# kanal_v2.net
KiCad netlist of a schematic drawn in EAGLE
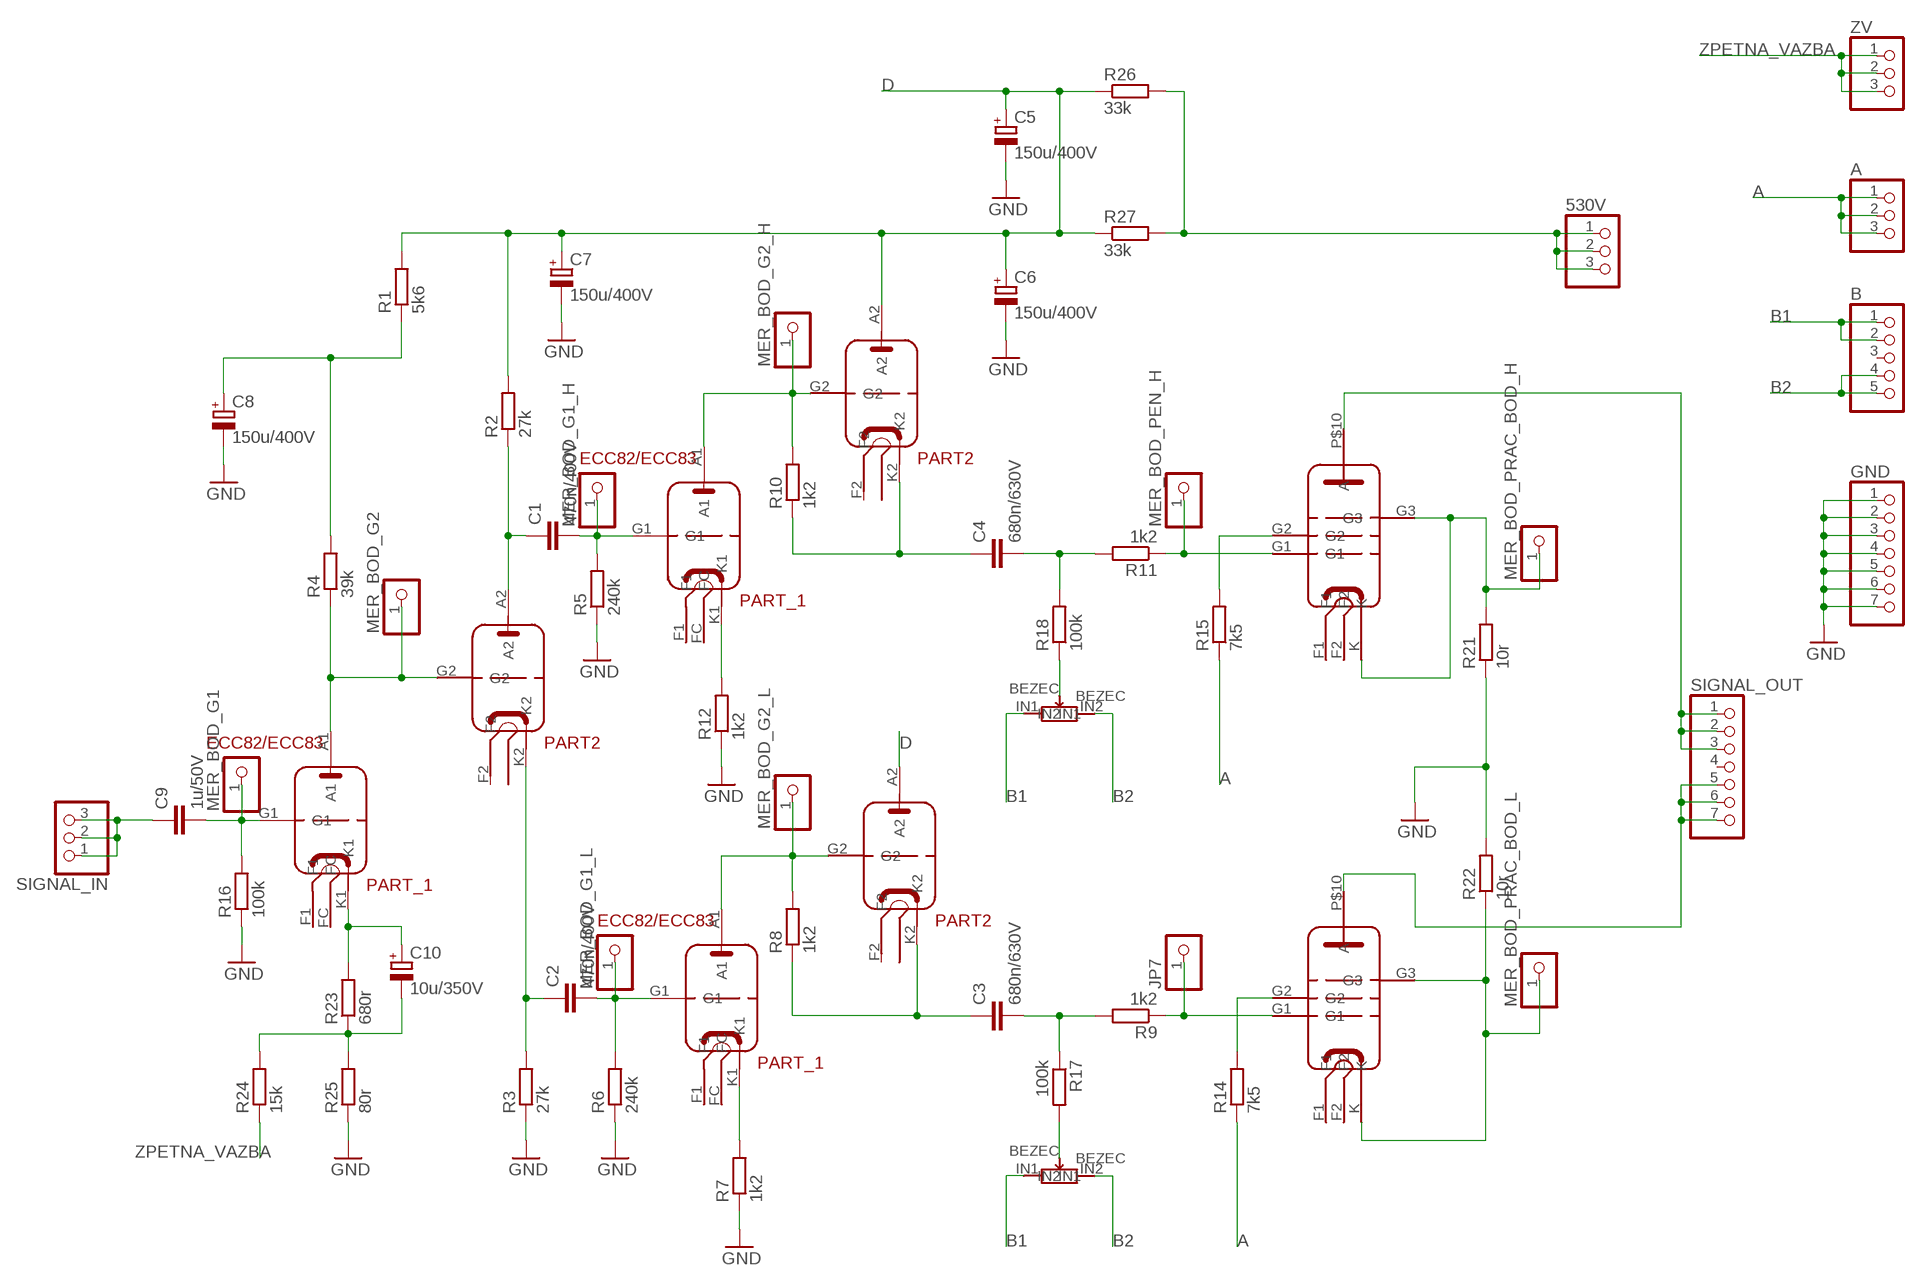
[diagram p0: schematic, sheet 1]

(export (version "E")
  (design (tool "Eeschema 10.0.6"))
  (components
    (comp (ref "530V")
      (value "PINHD-1X3")
      (footprint "eagle-import:1X03")
      (libsource (lib "eagle-import") (part "PINHD-1X3"))
    )
    (comp (ref "A")
      (value "PINHD-1X3")
      (footprint "eagle-import:1X03")
      (libsource (lib "eagle-import") (part "PINHD-1X3"))
    )
    (comp (ref "B")
      (value "PINHD-1X5")
      (footprint "eagle-import:1X05")
      (libsource (lib "eagle-import") (part "PINHD-1X5"))
    )
    (comp (ref "C1")
      (value "470n/400V")
      (footprint "eagle-import:C15B7")
      (libsource (lib "eagle-import") (part "C15/7"))
    )
    (comp (ref "C2")
      (value "470n/400V")
      (footprint "eagle-import:C15B7")
      (libsource (lib "eagle-import") (part "C15/7"))
    )
    (comp (ref "C3")
      (value "680n/630V")
      (footprint "eagle-import:C27.5B11")
      (libsource (lib "eagle-import") (part "C27/11"))
    )
    (comp (ref "C4")
      (value "680n/630V")
      (footprint "eagle-import:C27.5B11")
      (libsource (lib "eagle-import") (part "C27/11"))
    )
    (comp (ref "C5")
      (value "150u/400V")
      (footprint "eagle-import:EB25D")
      (libsource (lib "eagle-import") (part "resistor_CPOL-EUE10-25"))
    )
    (comp (ref "C6")
      (value "150u/400V")
      (footprint "eagle-import:EB25D")
      (libsource (lib "eagle-import") (part "resistor_CPOL-EUE10-25"))
    )
    (comp (ref "C7")
      (value "150u/400V")
      (footprint "eagle-import:EB25D")
      (libsource (lib "eagle-import") (part "resistor_CPOL-EUE10-25"))
    )
    (comp (ref "C8")
      (value "150u/400V")
      (footprint "eagle-import:EB25D")
      (libsource (lib "eagle-import") (part "resistor_CPOL-EUE10-25"))
    )
    (comp (ref "C9")
      (value "1u/50V")
      (footprint "eagle-import:C5B3.5")
      (libsource (lib "eagle-import") (part "C5/3.5"))
    )
    (comp (ref "C10")
      (value "10u/350V")
      (footprint "eagle-import:E5-10,5")
      (libsource (lib "eagle-import") (part "CPOL-EUE5-10.5"))
    )
    (comp (ref "GND")
      (value "PINHD-1X7")
      (footprint "eagle-import:1X07")
      (libsource (lib "eagle-import") (part "PINHD-1X7"))
    )
    (comp (ref "JP7")
      (value "PINHD-1X1")
      (footprint "eagle-import:1X01")
      (libsource (lib "eagle-import") (part "PINHD-1X1"))
    )
    (comp (ref "MER_BOD_G1")
      (value "PINHD-1X1")
      (footprint "eagle-import:1X01")
      (libsource (lib "eagle-import") (part "PINHD-1X1"))
    )
    (comp (ref "MER_BOD_G1_H")
      (value "PINHD-1X1")
      (footprint "eagle-import:1X01")
      (libsource (lib "eagle-import") (part "PINHD-1X1"))
    )
    (comp (ref "MER_BOD_G1_L")
      (value "PINHD-1X1")
      (footprint "eagle-import:1X01")
      (libsource (lib "eagle-import") (part "PINHD-1X1"))
    )
    (comp (ref "MER_BOD_G2")
      (value "PINHD-1X1")
      (footprint "eagle-import:1X01")
      (libsource (lib "eagle-import") (part "PINHD-1X1"))
    )
    (comp (ref "MER_BOD_G2_H")
      (value "PINHD-1X1")
      (footprint "eagle-import:1X01")
      (libsource (lib "eagle-import") (part "PINHD-1X1"))
    )
    (comp (ref "MER_BOD_G2_L")
      (value "PINHD-1X1")
      (footprint "eagle-import:1X01")
      (libsource (lib "eagle-import") (part "PINHD-1X1"))
    )
    (comp (ref "MER_BOD_PEN_H")
      (value "PINHD-1X1")
      (footprint "eagle-import:1X01")
      (libsource (lib "eagle-import") (part "PINHD-1X1"))
    )
    (comp (ref "MER_BOD_PRAC_BOD_H")
      (value "PINHD-1X1")
      (footprint "eagle-import:1X01")
      (libsource (lib "eagle-import") (part "PINHD-1X1"))
    )
    (comp (ref "MER_BOD_PRAC_BOD_L")
      (value "PINHD-1X1")
      (footprint "eagle-import:1X01")
      (libsource (lib "eagle-import") (part "PINHD-1X1"))
    )
    (comp (ref "R1")
      (value "5k6")
      (footprint "eagle-import:0309_10")
      (libsource (lib "eagle-import") (part "R-EU_0309/10"))
    )
    (comp (ref "R2")
      (value "27k")
      (footprint "eagle-import:0309_10")
      (libsource (lib "eagle-import") (part "R-EU_0309/10"))
    )
    (comp (ref "R3")
      (value "27k")
      (footprint "eagle-import:0309_10")
      (libsource (lib "eagle-import") (part "R-EU_0309/10"))
    )
    (comp (ref "R4")
      (value "39k")
      (footprint "eagle-import:0309_10")
      (libsource (lib "eagle-import") (part "R-EU_0309/10"))
    )
    (comp (ref "R5")
      (value "240k")
      (footprint "eagle-import:0309_10")
      (libsource (lib "eagle-import") (part "R-EU_0309/10"))
    )
    (comp (ref "R6")
      (value "240k")
      (footprint "eagle-import:0309_10")
      (libsource (lib "eagle-import") (part "R-EU_0309/10"))
    )
    (comp (ref "R7")
      (value "1k2")
      (footprint "eagle-import:0309_10")
      (libsource (lib "eagle-import") (part "R-EU_0309/10"))
    )
    (comp (ref "R8")
      (value "1k2")
      (footprint "eagle-import:0309_10")
      (libsource (lib "eagle-import") (part "R-EU_0309/10"))
    )
    (comp (ref "R9")
      (value "1k2")
      (footprint "eagle-import:0309_10")
      (libsource (lib "eagle-import") (part "R-EU_0309/10"))
    )
    (comp (ref "R10")
      (value "1k2")
      (footprint "eagle-import:0309_10")
      (libsource (lib "eagle-import") (part "R-EU_0309/10"))
    )
    (comp (ref "R11")
      (value "1k2")
      (footprint "eagle-import:0309_10")
      (libsource (lib "eagle-import") (part "R-EU_0309/10"))
    )
    (comp (ref "R12")
      (value "1k2")
      (footprint "eagle-import:0309_10")
      (libsource (lib "eagle-import") (part "R-EU_0309/10"))
    )
    (comp (ref "R14")
      (value "7k5")
      (footprint "eagle-import:0309_10")
      (libsource (lib "eagle-import") (part "R-EU_0309/10"))
    )
    (comp (ref "R15")
      (value "7k5")
      (footprint "eagle-import:0309_10")
      (libsource (lib "eagle-import") (part "R-EU_0309/10"))
    )
    (comp (ref "R16")
      (value "100k")
      (footprint "eagle-import:0309_10")
      (libsource (lib "eagle-import") (part "R-EU_0309/10"))
    )
    (comp (ref "R17")
      (value "100k")
      (footprint "eagle-import:0309_10")
      (libsource (lib "eagle-import") (part "R-EU_0309/10"))
    )
    (comp (ref "R18")
      (value "100k")
      (footprint "eagle-import:0309_10")
      (libsource (lib "eagle-import") (part "R-EU_0309/10"))
    )
    (comp (ref "R21")
      (value "10r")
      (footprint "eagle-import:0309_10")
      (libsource (lib "eagle-import") (part "R-EU_0309/10"))
    )
    (comp (ref "R22")
      (value "10r")
      (footprint "eagle-import:0309_10")
      (libsource (lib "eagle-import") (part "R-EU_0309/10"))
    )
    (comp (ref "R23")
      (value "680r")
      (footprint "eagle-import:0309_10")
      (libsource (lib "eagle-import") (part "R-EU_0309/10"))
    )
    (comp (ref "R24")
      (value "15k")
      (footprint "eagle-import:0309_10")
      (libsource (lib "eagle-import") (part "R-EU_0309/10"))
    )
    (comp (ref "R25")
      (value "80r")
      (footprint "eagle-import:0309_10")
      (libsource (lib "eagle-import") (part "R-EU_0309/10"))
    )
    (comp (ref "R26")
      (value "33k")
      (footprint "eagle-import:0309_10")
      (libsource (lib "eagle-import") (part "R-EU_0309/10"))
    )
    (comp (ref "R27")
      (value "33k")
      (footprint "eagle-import:0309_10")
      (libsource (lib "eagle-import") (part "R-EU_0309/10"))
    )
    (comp (ref "SIGNAL_IN")
      (value "PINHD-1X3")
      (footprint "eagle-import:1X03")
      (libsource (lib "eagle-import") (part "PINHD-1X3"))
    )
    (comp (ref "SIGNAL_OUT")
      (value "PINHD-1X7")
      (footprint "eagle-import:1X07")
      (libsource (lib "eagle-import") (part "PINHD-1X7"))
    )
    (comp (ref "U$1")
      (value "ECC82")
      (footprint "eagle-import:ECC82_PACKAGE")
      (libsource (lib "eagle-import") (part "ECC82"))
    )
    (comp (ref "U$2")
      (value "ECC83")
      (footprint "eagle-import:ECC82_PACKAGE")
      (libsource (lib "eagle-import") (part "ECC83"))
    )
    (comp (ref "U$3")
      (value "ECC83")
      (footprint "eagle-import:ECC82_PACKAGE")
      (libsource (lib "eagle-import") (part "ECC83"))
    )
    (comp (ref "U$4")
      (value "PL509")
      (footprint "eagle-import:PL509_PACKAGE")
      (libsource (lib "eagle-import") (part "PL509"))
    )
    (comp (ref "U$5")
      (value "PL509")
      (footprint "eagle-import:PL509_PACKAGE")
      (libsource (lib "eagle-import") (part "PL509"))
    )
    (comp (ref "U$6")
      (value "TRIMMER")
      (footprint "eagle-import:TRIMMER_15X15_PACKAGE")
      (libsource (lib "eagle-import") (part "TRIMMER"))
    )
    (comp (ref "U$7")
      (value "TRIMMER")
      (footprint "eagle-import:TRIMMER_15X15_PACKAGE")
      (libsource (lib "eagle-import") (part "TRIMMER"))
    )
    (comp (ref "ZV")
      (value "PINHD-1X3")
      (footprint "eagle-import:1X03")
      (libsource (lib "eagle-import") (part "PINHD-1X3"))
    )
  )
  (nets
    (net (code "1") (name "/A") (class "Default")
      (node (ref "A") (pin "1") (pinfunction "1_1") (pintype "passive"))
      (node (ref "A") (pin "2") (pinfunction "2_2") (pintype "passive"))
      (node (ref "A") (pin "3") (pinfunction "3_3") (pintype "passive"))
      (node (ref "R14") (pin "1") (pinfunction "1_1") (pintype "passive"))
      (node (ref "R15") (pin "1") (pinfunction "1_1") (pintype "passive"))
    )
    (net (code "2") (name "/B1") (class "Default")
      (node (ref "B") (pin "1") (pinfunction "1_1") (pintype "passive"))
      (node (ref "B") (pin "2") (pinfunction "2_2") (pintype "passive"))
      (node (ref "U$6") (pin "IN1") (pinfunction "IN1_IN1") (pintype "bidirectional"))
      (node (ref "U$7") (pin "IN1") (pinfunction "IN1_IN1") (pintype "bidirectional"))
    )
    (net (code "3") (name "/B2") (class "Default")
      (node (ref "B") (pin "4") (pinfunction "4_4") (pintype "passive"))
      (node (ref "B") (pin "5") (pinfunction "5_5") (pintype "passive"))
      (node (ref "U$6") (pin "IN2") (pinfunction "IN2_IN2") (pintype "bidirectional"))
      (node (ref "U$7") (pin "IN2") (pinfunction "IN2_IN2") (pintype "bidirectional"))
    )
    (net (code "4") (name "/D") (class "Default")
      (node (ref "C5") (pin "+") (pinfunction "+_+") (pintype "passive"))
      (node (ref "C6") (pin "+") (pinfunction "+_+") (pintype "passive"))
      (node (ref "C7") (pin "+") (pinfunction "+_+") (pintype "passive"))
      (node (ref "R1") (pin "2") (pinfunction "2_2") (pintype "passive"))
      (node (ref "R2") (pin "2") (pinfunction "2_2") (pintype "passive"))
      (node (ref "R26") (pin "1") (pinfunction "1_1") (pintype "passive"))
      (node (ref "R27") (pin "1") (pinfunction "1_1") (pintype "passive"))
      (node (ref "U$2") (pin "A2") (pinfunction "A2_A2") (pintype "bidirectional"))
      (node (ref "U$3") (pin "A2") (pinfunction "A2_A2") (pintype "bidirectional"))
    )
    (net (code "5") (name "/ZPETNA_VAZBA") (class "Default")
      (node (ref "R24") (pin "1") (pinfunction "1_1") (pintype "passive"))
      (node (ref "ZV") (pin "1") (pinfunction "1_1") (pintype "passive"))
      (node (ref "ZV") (pin "2") (pinfunction "2_2") (pintype "passive"))
      (node (ref "ZV") (pin "3") (pinfunction "3_3") (pintype "passive"))
    )
    (net (code "6") (name "GND") (class "Default")
      (node (ref "C5") (pin "-") (pinfunction "-_-") (pintype "passive"))
      (node (ref "C6") (pin "-") (pinfunction "-_-") (pintype "passive"))
      (node (ref "C7") (pin "-") (pinfunction "-_-") (pintype "passive"))
      (node (ref "C8") (pin "-") (pinfunction "-_-") (pintype "passive"))
      (node (ref "GND") (pin "1") (pinfunction "1_1") (pintype "passive"))
      (node (ref "GND") (pin "2") (pinfunction "2_2") (pintype "passive"))
      (node (ref "GND") (pin "3") (pinfunction "3_3") (pintype "passive"))
      (node (ref "GND") (pin "4") (pinfunction "4_4") (pintype "passive"))
      (node (ref "GND") (pin "5") (pinfunction "5_5") (pintype "passive"))
      (node (ref "GND") (pin "6") (pinfunction "6_6") (pintype "passive"))
      (node (ref "GND") (pin "7") (pinfunction "7_7") (pintype "passive"))
      (node (ref "R12") (pin "1") (pinfunction "1_1") (pintype "passive"))
      (node (ref "R16") (pin "1") (pinfunction "1_1") (pintype "passive"))
      (node (ref "R21") (pin "1") (pinfunction "1_1") (pintype "passive"))
      (node (ref "R22") (pin "2") (pinfunction "2_2") (pintype "passive"))
      (node (ref "R25") (pin "1") (pinfunction "1_1") (pintype "passive"))
      (node (ref "R3") (pin "1") (pinfunction "1_1") (pintype "passive"))
      (node (ref "R5") (pin "1") (pinfunction "1_1") (pintype "passive"))
      (node (ref "R6") (pin "1") (pinfunction "1_1") (pintype "passive"))
      (node (ref "R7") (pin "1") (pinfunction "1_1") (pintype "passive"))
    )
    (net (code "7") (name "Net-(530V-Pad1)") (class "Default")
      (node (ref "530V") (pin "1") (pinfunction "1_1") (pintype "passive"))
      (node (ref "530V") (pin "2") (pinfunction "2_2") (pintype "passive"))
      (node (ref "530V") (pin "3") (pinfunction "3_3") (pintype "passive"))
      (node (ref "R26") (pin "2") (pinfunction "2_2") (pintype "passive"))
      (node (ref "R27") (pin "2") (pinfunction "2_2") (pintype "passive"))
    )
    (net (code "8") (name "Net-(C1-Pad1)") (class "Default")
      (node (ref "C1") (pin "1") (pinfunction "1_1") (pintype "passive"))
      (node (ref "R2") (pin "1") (pinfunction "1_1") (pintype "passive"))
      (node (ref "U$1") (pin "A2") (pinfunction "A2_A2") (pintype "bidirectional"))
    )
    (net (code "9") (name "Net-(C1-Pad2)") (class "Default")
      (node (ref "C1") (pin "2") (pinfunction "2_2") (pintype "passive"))
      (node (ref "MER_BOD_G1_H") (pin "1") (pinfunction "1_1") (pintype "passive"))
      (node (ref "R5") (pin "2") (pinfunction "2_2") (pintype "passive"))
      (node (ref "U$2") (pin "G1") (pinfunction "G1_G1") (pintype "bidirectional"))
    )
    (net (code "10") (name "Net-(C2-Pad1)") (class "Default")
      (node (ref "C2") (pin "1") (pinfunction "1_1") (pintype "passive"))
      (node (ref "R3") (pin "2") (pinfunction "2_2") (pintype "passive"))
      (node (ref "U$1") (pin "K2") (pinfunction "K2_K2") (pintype "bidirectional"))
    )
    (net (code "11") (name "Net-(C2-Pad2)") (class "Default")
      (node (ref "C2") (pin "2") (pinfunction "2_2") (pintype "passive"))
      (node (ref "MER_BOD_G1_L") (pin "1") (pinfunction "1_1") (pintype "passive"))
      (node (ref "R6") (pin "2") (pinfunction "2_2") (pintype "passive"))
      (node (ref "U$3") (pin "G1") (pinfunction "G1_G1") (pintype "bidirectional"))
    )
    (net (code "12") (name "Net-(C3-Pad1)") (class "Default")
      (node (ref "C3") (pin "1") (pinfunction "1_1") (pintype "passive"))
      (node (ref "R8") (pin "1") (pinfunction "1_1") (pintype "passive"))
      (node (ref "U$3") (pin "K2") (pinfunction "K2_K2") (pintype "bidirectional"))
    )
    (net (code "13") (name "Net-(C3-Pad2)") (class "Default")
      (node (ref "C3") (pin "2") (pinfunction "2_2") (pintype "passive"))
      (node (ref "R17") (pin "1") (pinfunction "1_1") (pintype "passive"))
      (node (ref "R9") (pin "2") (pinfunction "2_2") (pintype "passive"))
    )
    (net (code "14") (name "Net-(C4-Pad1)") (class "Default")
      (node (ref "C4") (pin "1") (pinfunction "1_1") (pintype "passive"))
      (node (ref "R10") (pin "1") (pinfunction "1_1") (pintype "passive"))
      (node (ref "U$2") (pin "K2") (pinfunction "K2_K2") (pintype "bidirectional"))
    )
    (net (code "15") (name "Net-(C4-Pad2)") (class "Default")
      (node (ref "C4") (pin "2") (pinfunction "2_2") (pintype "passive"))
      (node (ref "R11") (pin "2") (pinfunction "2_2") (pintype "passive"))
      (node (ref "R18") (pin "2") (pinfunction "2_2") (pintype "passive"))
    )
    (net (code "16") (name "Net-(C8-Pad+)") (class "Default")
      (node (ref "C8") (pin "+") (pinfunction "+_+") (pintype "passive"))
      (node (ref "R1") (pin "1") (pinfunction "1_1") (pintype "passive"))
      (node (ref "R4") (pin "2") (pinfunction "2_2") (pintype "passive"))
    )
    (net (code "17") (name "Net-(C9-Pad1)") (class "Default")
      (node (ref "C9") (pin "1") (pinfunction "1_1") (pintype "passive"))
      (node (ref "SIGNAL_IN") (pin "1") (pinfunction "1_1") (pintype "passive"))
      (node (ref "SIGNAL_IN") (pin "2") (pinfunction "2_2") (pintype "passive"))
      (node (ref "SIGNAL_IN") (pin "3") (pinfunction "3_3") (pintype "passive"))
    )
    (net (code "18") (name "Net-(C9-Pad2)") (class "Default")
      (node (ref "C9") (pin "2") (pinfunction "2_2") (pintype "passive"))
      (node (ref "MER_BOD_G1") (pin "1") (pinfunction "1_1") (pintype "passive"))
      (node (ref "R16") (pin "2") (pinfunction "2_2") (pintype "passive"))
      (node (ref "U$1") (pin "G1") (pinfunction "G1_G1") (pintype "bidirectional"))
    )
    (net (code "19") (name "Net-(C10-Pad+)") (class "Default")
      (node (ref "C10") (pin "+") (pinfunction "+_+") (pintype "passive"))
      (node (ref "R23") (pin "2") (pinfunction "2_2") (pintype "passive"))
      (node (ref "U$1") (pin "K1") (pinfunction "K1_K1") (pintype "bidirectional"))
    )
    (net (code "20") (name "Net-(C10-Pad-)") (class "Default")
      (node (ref "C10") (pin "-") (pinfunction "-_-") (pintype "passive"))
      (node (ref "R23") (pin "1") (pinfunction "1_1") (pintype "passive"))
      (node (ref "R24") (pin "2") (pinfunction "2_2") (pintype "passive"))
      (node (ref "R25") (pin "2") (pinfunction "2_2") (pintype "passive"))
    )
    (net (code "21") (name "Net-(JP7-Pad1)") (class "Default")
      (node (ref "JP7") (pin "1") (pinfunction "1_1") (pintype "passive"))
      (node (ref "R9") (pin "1") (pinfunction "1_1") (pintype "passive"))
      (node (ref "U$5") (pin "G1") (pinfunction "G1_G1") (pintype "bidirectional"))
    )
    (net (code "22") (name "Net-(MER_BOD_G2-Pad1)") (class "Default")
      (node (ref "MER_BOD_G2") (pin "1") (pinfunction "1_1") (pintype "passive"))
      (node (ref "R4") (pin "1") (pinfunction "1_1") (pintype "passive"))
      (node (ref "U$1") (pin "A1") (pinfunction "A1_A1") (pintype "bidirectional"))
      (node (ref "U$1") (pin "G2") (pinfunction "G2_G2") (pintype "bidirectional"))
    )
    (net (code "23") (name "Net-(MER_BOD_G2_H-Pad1)") (class "Default")
      (node (ref "MER_BOD_G2_H") (pin "1") (pinfunction "1_1") (pintype "passive"))
      (node (ref "R10") (pin "2") (pinfunction "2_2") (pintype "passive"))
      (node (ref "U$2") (pin "A1") (pinfunction "A1_A1") (pintype "bidirectional"))
      (node (ref "U$2") (pin "G2") (pinfunction "G2_G2") (pintype "bidirectional"))
    )
    (net (code "24") (name "Net-(MER_BOD_G2_L-Pad1)") (class "Default")
      (node (ref "MER_BOD_G2_L") (pin "1") (pinfunction "1_1") (pintype "passive"))
      (node (ref "R8") (pin "2") (pinfunction "2_2") (pintype "passive"))
      (node (ref "U$3") (pin "A1") (pinfunction "A1_A1") (pintype "bidirectional"))
      (node (ref "U$3") (pin "G2") (pinfunction "G2_G2") (pintype "bidirectional"))
    )
    (net (code "25") (name "Net-(MER_BOD_PEN_H-Pad1)") (class "Default")
      (node (ref "MER_BOD_PEN_H") (pin "1") (pinfunction "1_1") (pintype "passive"))
      (node (ref "R11") (pin "1") (pinfunction "1_1") (pintype "passive"))
      (node (ref "U$4") (pin "G1") (pinfunction "G1_G1") (pintype "bidirectional"))
    )
    (net (code "26") (name "Net-(MER_BOD_PRAC_BOD_H-Pad1)") (class "Default")
      (node (ref "MER_BOD_PRAC_BOD_H") (pin "1") (pinfunction "1_1") (pintype "passive"))
      (node (ref "R21") (pin "2") (pinfunction "2_2") (pintype "passive"))
      (node (ref "U$4") (pin "G3") (pinfunction "G3_G3") (pintype "bidirectional"))
      (node (ref "U$4") (pin "K") (pinfunction "K_K") (pintype "bidirectional"))
    )
    (net (code "27") (name "Net-(MER_BOD_PRAC_BOD_L-Pad1)") (class "Default")
      (node (ref "MER_BOD_PRAC_BOD_L") (pin "1") (pinfunction "1_1") (pintype "passive"))
      (node (ref "R22") (pin "1") (pinfunction "1_1") (pintype "passive"))
      (node (ref "U$5") (pin "G3") (pinfunction "G3_G3") (pintype "bidirectional"))
      (node (ref "U$5") (pin "K") (pinfunction "K_K") (pintype "bidirectional"))
    )
    (net (code "28") (name "Net-(R7-Pad2)") (class "Default")
      (node (ref "R7") (pin "2") (pinfunction "2_2") (pintype "passive"))
      (node (ref "U$3") (pin "K1") (pinfunction "K1_K1") (pintype "bidirectional"))
    )
    (net (code "29") (name "Net-(R12-Pad2)") (class "Default")
      (node (ref "R12") (pin "2") (pinfunction "2_2") (pintype "passive"))
      (node (ref "U$2") (pin "K1") (pinfunction "K1_K1") (pintype "bidirectional"))
    )
    (net (code "30") (name "Net-(R14-Pad2)") (class "Default")
      (node (ref "R14") (pin "2") (pinfunction "2_2") (pintype "passive"))
      (node (ref "U$5") (pin "G2") (pinfunction "G2_G2") (pintype "bidirectional"))
    )
    (net (code "31") (name "Net-(R15-Pad2)") (class "Default")
      (node (ref "R15") (pin "2") (pinfunction "2_2") (pintype "passive"))
      (node (ref "U$4") (pin "G2") (pinfunction "G2_G2") (pintype "bidirectional"))
    )
    (net (code "32") (name "Net-(R17-Pad2)") (class "Default")
      (node (ref "R17") (pin "2") (pinfunction "2_2") (pintype "passive"))
      (node (ref "U$6") (pin "BEZEC") (pinfunction "BEZEC_BEZEC") (pintype "bidirectional"))
    )
    (net (code "33") (name "Net-(R18-Pad1)") (class "Default")
      (node (ref "R18") (pin "1") (pinfunction "1_1") (pintype "passive"))
      (node (ref "U$7") (pin "BEZEC") (pinfunction "BEZEC_BEZEC") (pintype "bidirectional"))
    )
    (net (code "34") (name "Net-(U$4-A)") (class "Default")
      (node (ref "SIGNAL_OUT") (pin "1") (pinfunction "1_1") (pintype "passive"))
      (node (ref "SIGNAL_OUT") (pin "2") (pinfunction "2_2") (pintype "passive"))
      (node (ref "SIGNAL_OUT") (pin "3") (pinfunction "3_3") (pintype "passive"))
      (node (ref "U$4") (pin "P$10") (pinfunction "A_P$10") (pintype "bidirectional"))
    )
    (net (code "35") (name "Net-(U$5-A)") (class "Default")
      (node (ref "SIGNAL_OUT") (pin "5") (pinfunction "5_5") (pintype "passive"))
      (node (ref "SIGNAL_OUT") (pin "6") (pinfunction "6_6") (pintype "passive"))
      (node (ref "SIGNAL_OUT") (pin "7") (pinfunction "7_7") (pintype "passive"))
      (node (ref "U$5") (pin "P$10") (pinfunction "A_P$10") (pintype "bidirectional"))
    )
    (net (code "36") (name "unconnected-(B-Pad3)") (class "Default")
      (node (ref "B") (pin "3") (pinfunction "3_3") (pintype "passive"))
    )
    (net (code "37") (name "unconnected-(SIGNAL_OUT-Pad4)") (class "Default")
      (node (ref "SIGNAL_OUT") (pin "4") (pinfunction "4_4") (pintype "passive"))
    )
    (net (code "38") (name "unconnected-(U$1-PadF1)") (class "Default")
      (node (ref "U$1") (pin "F1") (pinfunction "F1_F1") (pintype "bidirectional"))
    )
    (net (code "39") (name "unconnected-(U$1-PadF2)") (class "Default")
      (node (ref "U$1") (pin "F2") (pinfunction "F2_F2") (pintype "bidirectional"))
    )
    (net (code "40") (name "unconnected-(U$1-PadFC)") (class "Default")
      (node (ref "U$1") (pin "FC") (pinfunction "FC_FC") (pintype "bidirectional"))
    )
    (net (code "41") (name "unconnected-(U$2-PadF1)") (class "Default")
      (node (ref "U$2") (pin "F1") (pinfunction "F1_F1") (pintype "bidirectional"))
    )
    (net (code "42") (name "unconnected-(U$2-PadF2)") (class "Default")
      (node (ref "U$2") (pin "F2") (pinfunction "F2_F2") (pintype "bidirectional"))
    )
    (net (code "43") (name "unconnected-(U$2-PadFC)") (class "Default")
      (node (ref "U$2") (pin "FC") (pinfunction "FC_FC") (pintype "bidirectional"))
    )
    (net (code "44") (name "unconnected-(U$3-PadF1)") (class "Default")
      (node (ref "U$3") (pin "F1") (pinfunction "F1_F1") (pintype "bidirectional"))
    )
    (net (code "45") (name "unconnected-(U$3-PadF2)") (class "Default")
      (node (ref "U$3") (pin "F2") (pinfunction "F2_F2") (pintype "bidirectional"))
    )
    (net (code "46") (name "unconnected-(U$3-PadFC)") (class "Default")
      (node (ref "U$3") (pin "FC") (pinfunction "FC_FC") (pintype "bidirectional"))
    )
    (net (code "47") (name "unconnected-(U$4-PadF1)") (class "Default")
      (node (ref "U$4") (pin "F1") (pinfunction "F1_F1") (pintype "bidirectional"))
    )
    (net (code "48") (name "unconnected-(U$4-PadF2)") (class "Default")
      (node (ref "U$4") (pin "F2") (pinfunction "F2_F2") (pintype "bidirectional"))
    )
    (net (code "49") (name "unconnected-(U$5-PadF1)") (class "Default")
      (node (ref "U$5") (pin "F1") (pinfunction "F1_F1") (pintype "bidirectional"))
    )
    (net (code "50") (name "unconnected-(U$5-PadF2)") (class "Default")
      (node (ref "U$5") (pin "F2") (pinfunction "F2_F2") (pintype "bidirectional"))
    )
  )
)
